# Osilat_r.net
KiCad netlist of a schematic drawn in EAGLE
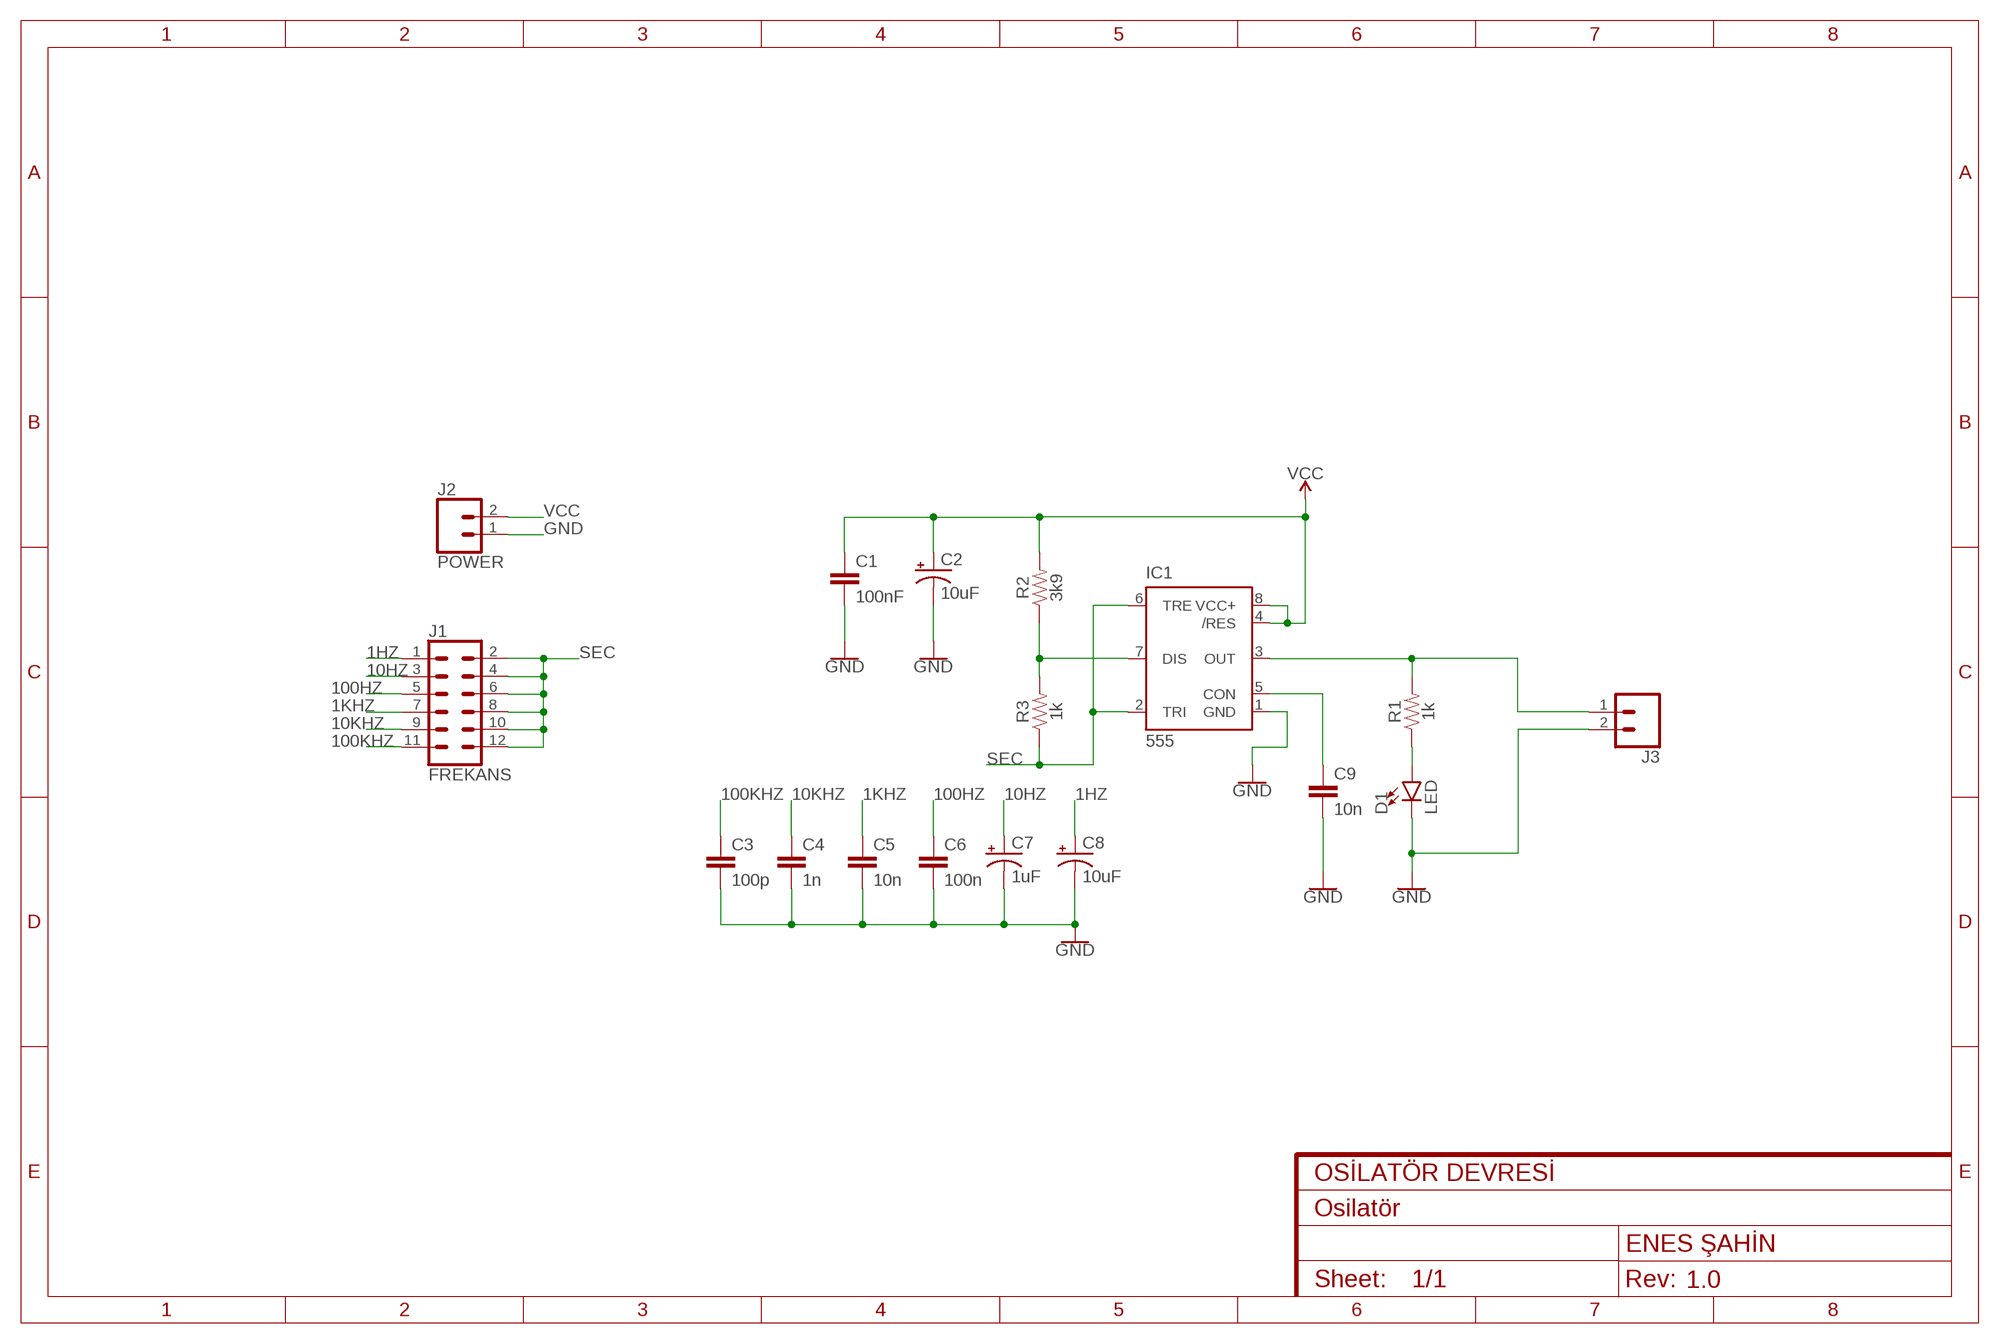
[diagram p0: schematic, sheet 1]

(export (version "E")
  (design (tool "Eeschema 10.0.6"))
  (components
    (comp (ref "C1")
      (value "100nF")
      (footprint "eagle-import:C2.5-3")
      (libsource (lib "eagle-import") (part "C2,5-3"))
    )
    (comp (ref "C2")
      (value "10uF")
      (footprint "eagle-import:CPOL-RADIAL-2.5MM-6.5MM")
      (libsource (lib "eagle-import") (part "100UF-POLAR-RADIAL-2.5MM-25V-20%"))
    )
    (comp (ref "C3")
      (value "100p")
      (footprint "eagle-import:C2.5-3")
      (libsource (lib "eagle-import") (part "C2,5-3"))
    )
    (comp (ref "C4")
      (value "1n")
      (footprint "eagle-import:C2.5-3")
      (libsource (lib "eagle-import") (part "C2,5-3"))
    )
    (comp (ref "C5")
      (value "10n")
      (footprint "eagle-import:C2.5-3")
      (libsource (lib "eagle-import") (part "C2,5-3"))
    )
    (comp (ref "C6")
      (value "100n")
      (footprint "eagle-import:C2.5-3")
      (libsource (lib "eagle-import") (part "C2,5-3"))
    )
    (comp (ref "C7")
      (value "1uF")
      (footprint "eagle-import:CPOL-RADIAL-2.5MM-6.5MM")
      (libsource (lib "eagle-import") (part "100UF-POLAR-RADIAL-2.5MM-25V-20%"))
    )
    (comp (ref "C8")
      (value "10uF")
      (footprint "eagle-import:CPOL-RADIAL-2.5MM-6.5MM")
      (libsource (lib "eagle-import") (part "100UF-POLAR-RADIAL-2.5MM-25V-20%"))
    )
    (comp (ref "C9")
      (value "10n")
      (footprint "eagle-import:C2.5-3")
      (libsource (lib "eagle-import") (part "C2,5-3"))
    )
    (comp (ref "D1")
      (value "LED")
      (footprint "eagle-import:LED_3MM-NS")
      (libsource (lib "eagle-import") (part "LED-3MM-NO_SILK"))
    )
    (comp (ref "IC1")
      (value "555")
      (footprint "eagle-import:DIP08-KIT")
      (libsource (lib "eagle-import") (part "555KIT"))
    )
    (comp (ref "J1")
      (value "FREKANS")
      (footprint "eagle-import:2X6")
      (libsource (lib "eagle-import") (part "CONN_06X2PTH_FEMALE"))
    )
    (comp (ref "J2")
      (value "POWER")
      (footprint "eagle-import:1X02")
      (libsource (lib "eagle-import") (part "CONN_02"))
    )
    (comp (ref "J3")
      (value "CONN_02")
      (footprint "eagle-import:1X02")
      (libsource (lib "eagle-import") (part "CONN_02"))
    )
    (comp (ref "R1")
      (value "1k")
      (footprint "eagle-import:AXIAL-0.3")
      (libsource (lib "eagle-import") (part "1KOHM-HORIZ-1/4W-1%"))
    )
    (comp (ref "R2")
      (value "3k9")
      (footprint "eagle-import:AXIAL-0.3")
      (libsource (lib "eagle-import") (part "1KOHM-HORIZ-1/4W-1%"))
    )
    (comp (ref "R3")
      (value "1k")
      (footprint "eagle-import:AXIAL-0.3")
      (libsource (lib "eagle-import") (part "1KOHM-HORIZ-1/4W-1%"))
    )
  )
  (nets
    (net (code "1") (name "/1HZ") (class "Default")
      (node (ref "C8") (pin "1") (pinfunction "+_1") (pintype "passive"))
      (node (ref "J1") (pin "1") (pinfunction "1_1") (pintype "passive"))
    )
    (net (code "2") (name "/1KHZ") (class "Default")
      (node (ref "C5") (pin "1") (pinfunction "1_1") (pintype "passive"))
      (node (ref "J1") (pin "7") (pinfunction "7_7") (pintype "passive"))
    )
    (net (code "3") (name "/10HZ") (class "Default")
      (node (ref "C7") (pin "1") (pinfunction "+_1") (pintype "passive"))
      (node (ref "J1") (pin "3") (pinfunction "3_3") (pintype "passive"))
    )
    (net (code "4") (name "/10KHZ") (class "Default")
      (node (ref "C4") (pin "1") (pinfunction "1_1") (pintype "passive"))
      (node (ref "J1") (pin "9") (pinfunction "9_9") (pintype "passive"))
    )
    (net (code "5") (name "/100HZ") (class "Default")
      (node (ref "C6") (pin "1") (pinfunction "1_1") (pintype "passive"))
      (node (ref "J1") (pin "5") (pinfunction "5_5") (pintype "passive"))
    )
    (net (code "6") (name "/100KHZ") (class "Default")
      (node (ref "C3") (pin "1") (pinfunction "1_1") (pintype "passive"))
      (node (ref "J1") (pin "11") (pinfunction "11_11") (pintype "passive"))
    )
    (net (code "7") (name "/SEC") (class "Default")
      (node (ref "IC1") (pin "2") (pinfunction "TRI_2") (pintype "input"))
      (node (ref "IC1") (pin "6") (pinfunction "TRE_6") (pintype "input"))
      (node (ref "J1") (pin "10") (pinfunction "10_10") (pintype "passive"))
      (node (ref "J1") (pin "12") (pinfunction "12_12") (pintype "passive"))
      (node (ref "J1") (pin "2") (pinfunction "2_2") (pintype "passive"))
      (node (ref "J1") (pin "4") (pinfunction "4_4") (pintype "passive"))
      (node (ref "J1") (pin "6") (pinfunction "6_6") (pintype "passive"))
      (node (ref "J1") (pin "8") (pinfunction "8_8") (pintype "passive"))
      (node (ref "R3") (pin "P$1") (pinfunction "1_P$1") (pintype "passive"))
    )
    (net (code "8") (name "GND") (class "Default")
      (node (ref "C1") (pin "2") (pinfunction "2_2") (pintype "passive"))
      (node (ref "C2") (pin "2") (pinfunction "-_2") (pintype "passive"))
      (node (ref "C3") (pin "2") (pinfunction "2_2") (pintype "passive"))
      (node (ref "C4") (pin "2") (pinfunction "2_2") (pintype "passive"))
      (node (ref "C5") (pin "2") (pinfunction "2_2") (pintype "passive"))
      (node (ref "C6") (pin "2") (pinfunction "2_2") (pintype "passive"))
      (node (ref "C7") (pin "2") (pinfunction "-_2") (pintype "passive"))
      (node (ref "C8") (pin "2") (pinfunction "-_2") (pintype "passive"))
      (node (ref "C9") (pin "2") (pinfunction "2_2") (pintype "passive"))
      (node (ref "D1") (pin "K") (pinfunction "C_K") (pintype "passive"))
      (node (ref "IC1") (pin "1") (pinfunction "GND_1") (pintype "power_in"))
      (node (ref "J2") (pin "1") (pinfunction "1_1") (pintype "passive"))
      (node (ref "J3") (pin "2") (pinfunction "2_2") (pintype "passive"))
    )
    (net (code "9") (name "Net-(IC1-CON)") (class "Default")
      (node (ref "C9") (pin "1") (pinfunction "1_1") (pintype "passive"))
      (node (ref "IC1") (pin "5") (pinfunction "CON_5") (pintype "input"))
    )
    (net (code "10") (name "Net-(IC1-DIS)") (class "Default")
      (node (ref "IC1") (pin "7") (pinfunction "DIS_7") (pintype "input"))
      (node (ref "R2") (pin "P$1") (pinfunction "1_P$1") (pintype "passive"))
      (node (ref "R3") (pin "P$2") (pinfunction "2_P$2") (pintype "passive"))
    )
    (net (code "11") (name "Net-(IC1-OUT)") (class "Default")
      (node (ref "IC1") (pin "3") (pinfunction "OUT_3") (pintype "output"))
      (node (ref "J3") (pin "1") (pinfunction "1_1") (pintype "passive"))
      (node (ref "R1") (pin "P$2") (pinfunction "2_P$2") (pintype "passive"))
    )
    (net (code "12") (name "Net-(R1-1)") (class "Default")
      (node (ref "D1") (pin "A") (pinfunction "A_A") (pintype "passive"))
      (node (ref "R1") (pin "P$1") (pinfunction "1_P$1") (pintype "passive"))
    )
    (net (code "13") (name "VCC") (class "Default")
      (node (ref "C1") (pin "1") (pinfunction "1_1") (pintype "passive"))
      (node (ref "C2") (pin "1") (pinfunction "+_1") (pintype "passive"))
      (node (ref "IC1") (pin "4") (pinfunction "/RES_4") (pintype "input"))
      (node (ref "IC1") (pin "8") (pinfunction "VCC+_8") (pintype "power_in"))
      (node (ref "J2") (pin "2") (pinfunction "2_2") (pintype "passive"))
      (node (ref "R2") (pin "P$2") (pinfunction "2_P$2") (pintype "passive"))
    )
  )
)
